# W021A.net
KiCad netlist of a schematic drawn in EAGLE
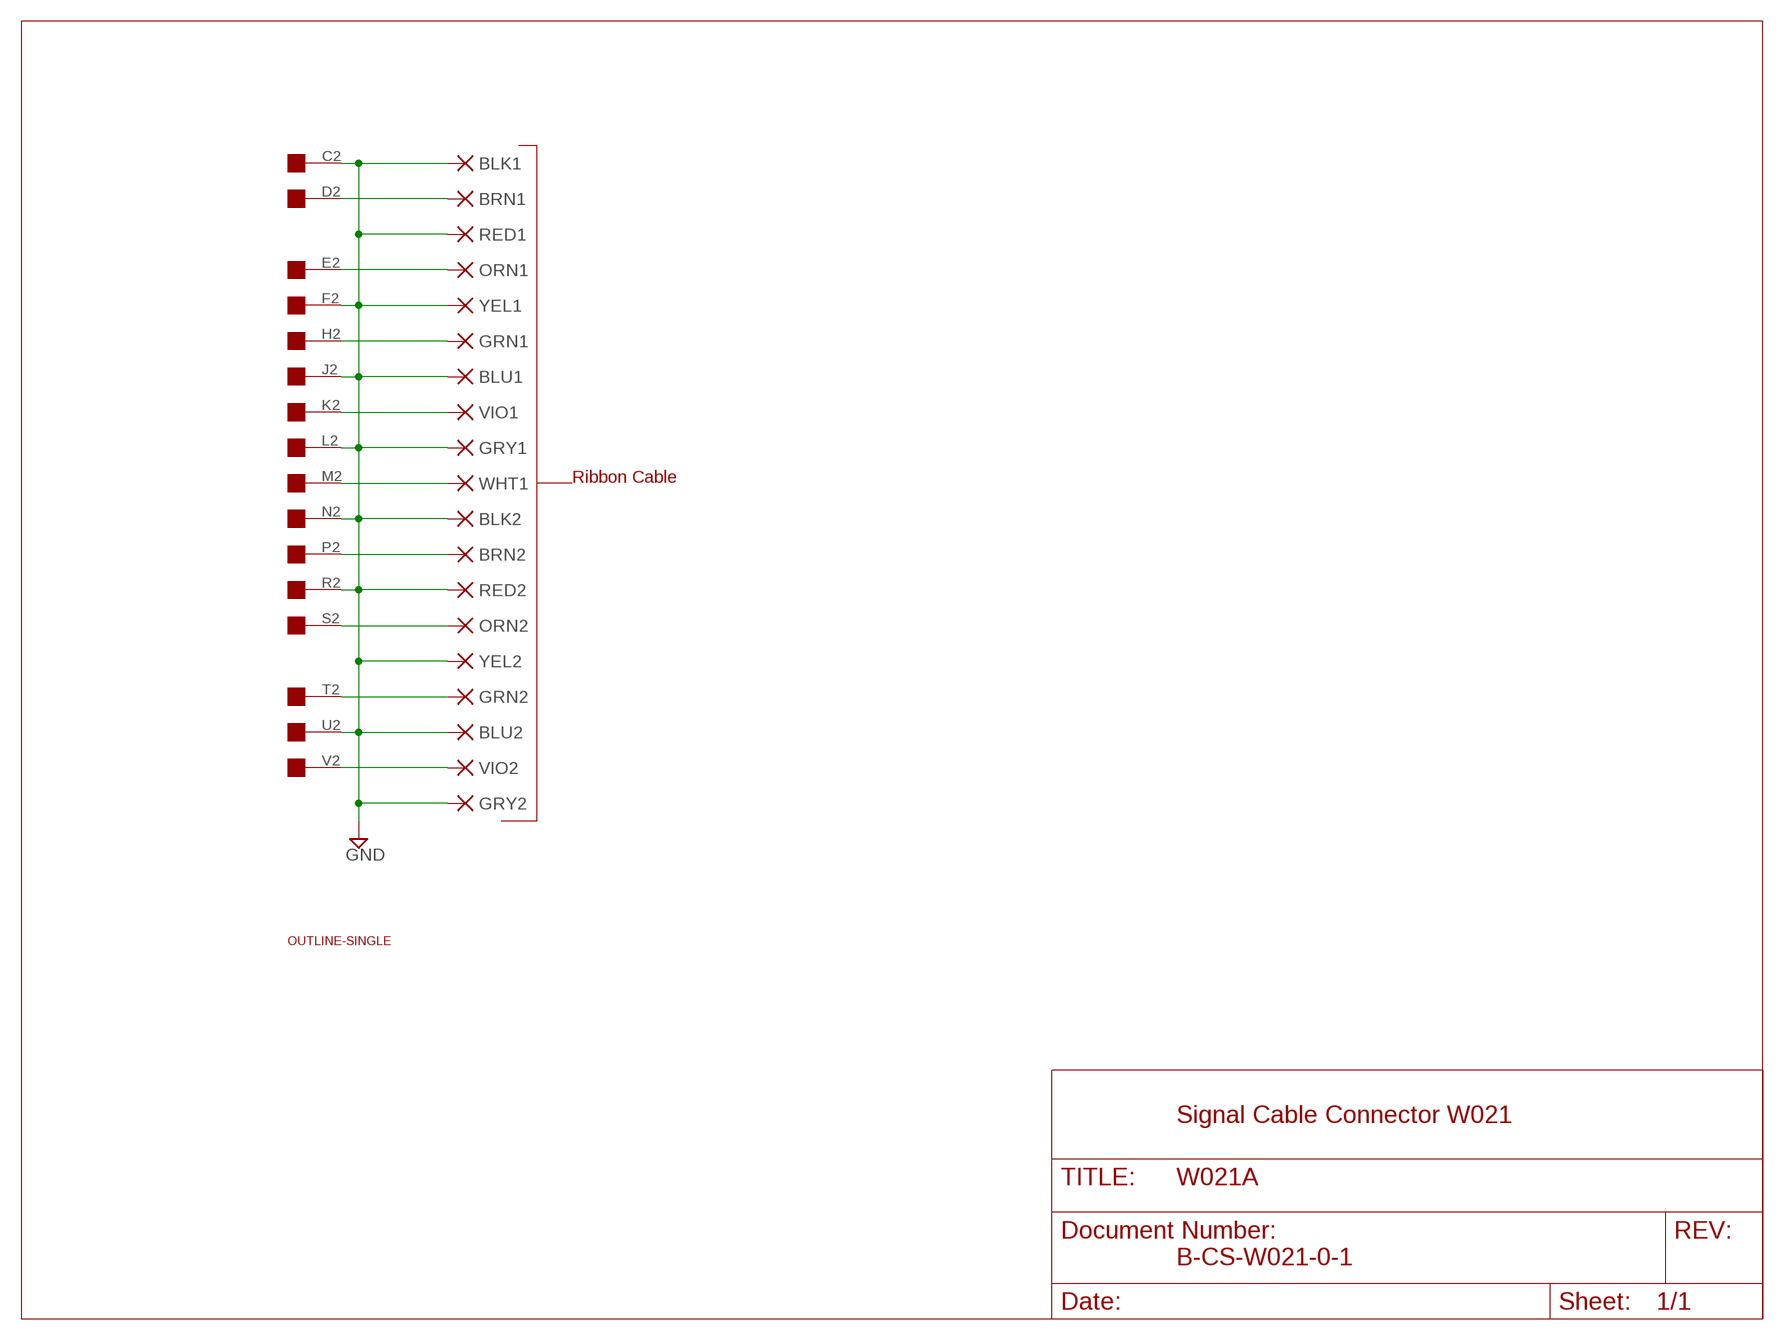
[diagram p0: schematic, sheet 1]

(export (version "E")
  (design (tool "Eeschema 10.0.6"))
  (components
    (comp (ref "BLK1")
      (value "PAD-0465")
      (footprint "eagle-import:0465")
      (libsource (lib "eagle-import") (part "PAD-0465"))
    )
    (comp (ref "BLK2")
      (value "PAD-0465")
      (footprint "eagle-import:0465")
      (libsource (lib "eagle-import") (part "PAD-0465"))
    )
    (comp (ref "BLU1")
      (value "PAD-0465")
      (footprint "eagle-import:0465")
      (libsource (lib "eagle-import") (part "PAD-0465"))
    )
    (comp (ref "BLU2")
      (value "PAD-0465")
      (footprint "eagle-import:0465")
      (libsource (lib "eagle-import") (part "PAD-0465"))
    )
    (comp (ref "BRN1")
      (value "PAD-0465")
      (footprint "eagle-import:0465")
      (libsource (lib "eagle-import") (part "PAD-0465"))
    )
    (comp (ref "BRN2")
      (value "PAD-0465")
      (footprint "eagle-import:0465")
      (libsource (lib "eagle-import") (part "PAD-0465"))
    )
    (comp (ref "GRN1")
      (value "PAD-0465")
      (footprint "eagle-import:0465")
      (libsource (lib "eagle-import") (part "PAD-0465"))
    )
    (comp (ref "GRN2")
      (value "PAD-0465")
      (footprint "eagle-import:0465")
      (libsource (lib "eagle-import") (part "PAD-0465"))
    )
    (comp (ref "GRY1")
      (value "PAD-0465")
      (footprint "eagle-import:0465")
      (libsource (lib "eagle-import") (part "PAD-0465"))
    )
    (comp (ref "GRY2")
      (value "PAD-0465")
      (footprint "eagle-import:0465")
      (libsource (lib "eagle-import") (part "PAD-0465"))
    )
    (comp (ref "ORN1")
      (value "PAD-0465")
      (footprint "eagle-import:0465")
      (libsource (lib "eagle-import") (part "PAD-0465"))
    )
    (comp (ref "ORN2")
      (value "PAD-0465")
      (footprint "eagle-import:0465")
      (libsource (lib "eagle-import") (part "PAD-0465"))
    )
    (comp (ref "RED1")
      (value "PAD-0465")
      (footprint "eagle-import:0465")
      (libsource (lib "eagle-import") (part "PAD-0465"))
    )
    (comp (ref "RED2")
      (value "PAD-0465")
      (footprint "eagle-import:0465")
      (libsource (lib "eagle-import") (part "PAD-0465"))
    )
    (comp (ref "U$1")
      (value "OUTLINE-SINGLE")
      (footprint "eagle-import:SINGLE")
      (libsource (lib "eagle-import") (part "OUTLINE-SINGLE"))
    )
    (comp (ref "U$2")
      (value "EDGE-1")
      (footprint "eagle-import:EDGE-CON1")
      (libsource (lib "eagle-import") (part "EDGE-1"))
    )
    (comp (ref "VIO1")
      (value "PAD-0465")
      (footprint "eagle-import:0465")
      (libsource (lib "eagle-import") (part "PAD-0465"))
    )
    (comp (ref "VIO2")
      (value "PAD-0465")
      (footprint "eagle-import:0465")
      (libsource (lib "eagle-import") (part "PAD-0465"))
    )
    (comp (ref "WHT1")
      (value "PAD-0465")
      (footprint "eagle-import:0465")
      (libsource (lib "eagle-import") (part "PAD-0465"))
    )
    (comp (ref "YEL1")
      (value "PAD-0465")
      (footprint "eagle-import:0465")
      (libsource (lib "eagle-import") (part "PAD-0465"))
    )
    (comp (ref "YEL2")
      (value "PAD-0465")
      (footprint "eagle-import:0465")
      (libsource (lib "eagle-import") (part "PAD-0465"))
    )
  )
  (nets
    (net (code "1") (name "GND") (class "Default")
      (node (ref "BLK1") (pin "P$1") (pinfunction "P_P$1") (pintype "passive"))
      (node (ref "BLK2") (pin "P$1") (pinfunction "P_P$1") (pintype "passive"))
      (node (ref "BLU1") (pin "P$1") (pinfunction "P_P$1") (pintype "passive"))
      (node (ref "BLU2") (pin "P$1") (pinfunction "P_P$1") (pintype "passive"))
      (node (ref "GRY1") (pin "P$1") (pinfunction "P_P$1") (pintype "passive"))
      (node (ref "GRY2") (pin "P$1") (pinfunction "P_P$1") (pintype "passive"))
      (node (ref "RED1") (pin "P$1") (pinfunction "P_P$1") (pintype "passive"))
      (node (ref "RED2") (pin "P$1") (pinfunction "P_P$1") (pintype "passive"))
      (node (ref "U$2") (pin "C2") (pinfunction "1_C2") (pintype "bidirectional"))
      (node (ref "U$2") (pin "F2") (pinfunction "1_F2") (pintype "bidirectional"))
      (node (ref "U$2") (pin "J2") (pinfunction "1_J2") (pintype "bidirectional"))
      (node (ref "U$2") (pin "L2") (pinfunction "1_L2") (pintype "bidirectional"))
      (node (ref "U$2") (pin "N2") (pinfunction "1_N2") (pintype "bidirectional"))
      (node (ref "U$2") (pin "R2") (pinfunction "1_R2") (pintype "bidirectional"))
      (node (ref "U$2") (pin "U2") (pinfunction "1_U2") (pintype "bidirectional"))
      (node (ref "YEL1") (pin "P$1") (pinfunction "P_P$1") (pintype "passive"))
      (node (ref "YEL2") (pin "P$1") (pinfunction "P_P$1") (pintype "passive"))
    )
    (net (code "2") (name "Net-(BRN1-P)") (class "Default")
      (node (ref "BRN1") (pin "P$1") (pinfunction "P_P$1") (pintype "passive"))
      (node (ref "U$2") (pin "D2") (pinfunction "1_D2") (pintype "bidirectional"))
    )
    (net (code "3") (name "Net-(BRN2-P)") (class "Default")
      (node (ref "BRN2") (pin "P$1") (pinfunction "P_P$1") (pintype "passive"))
      (node (ref "U$2") (pin "P2") (pinfunction "1_P2") (pintype "bidirectional"))
    )
    (net (code "4") (name "Net-(GRN1-P)") (class "Default")
      (node (ref "GRN1") (pin "P$1") (pinfunction "P_P$1") (pintype "passive"))
      (node (ref "U$2") (pin "H2") (pinfunction "1_H2") (pintype "bidirectional"))
    )
    (net (code "5") (name "Net-(GRN2-P)") (class "Default")
      (node (ref "GRN2") (pin "P$1") (pinfunction "P_P$1") (pintype "passive"))
      (node (ref "U$2") (pin "T2") (pinfunction "1_T2") (pintype "bidirectional"))
    )
    (net (code "6") (name "Net-(ORN1-P)") (class "Default")
      (node (ref "ORN1") (pin "P$1") (pinfunction "P_P$1") (pintype "passive"))
      (node (ref "U$2") (pin "E2") (pinfunction "1_E2") (pintype "bidirectional"))
    )
    (net (code "7") (name "Net-(ORN2-P)") (class "Default")
      (node (ref "ORN2") (pin "P$1") (pinfunction "P_P$1") (pintype "passive"))
      (node (ref "U$2") (pin "S2") (pinfunction "1_S2") (pintype "bidirectional"))
    )
    (net (code "8") (name "Net-(U$2I-1)") (class "Default")
      (node (ref "U$2") (pin "K2") (pinfunction "1_K2") (pintype "bidirectional"))
      (node (ref "VIO1") (pin "P$1") (pinfunction "P_P$1") (pintype "passive"))
    )
    (net (code "9") (name "Net-(U$2K-1)") (class "Default")
      (node (ref "U$2") (pin "M2") (pinfunction "1_M2") (pintype "bidirectional"))
      (node (ref "WHT1") (pin "P$1") (pinfunction "P_P$1") (pintype "passive"))
    )
    (net (code "10") (name "Net-(U$2R-1)") (class "Default")
      (node (ref "U$2") (pin "V2") (pinfunction "1_V2") (pintype "bidirectional"))
      (node (ref "VIO2") (pin "P$1") (pinfunction "P_P$1") (pintype "passive"))
    )
  )
)
